# Crumar_D9U_Drawbars.net
KiCad netlist of a schematic drawn in EAGLE
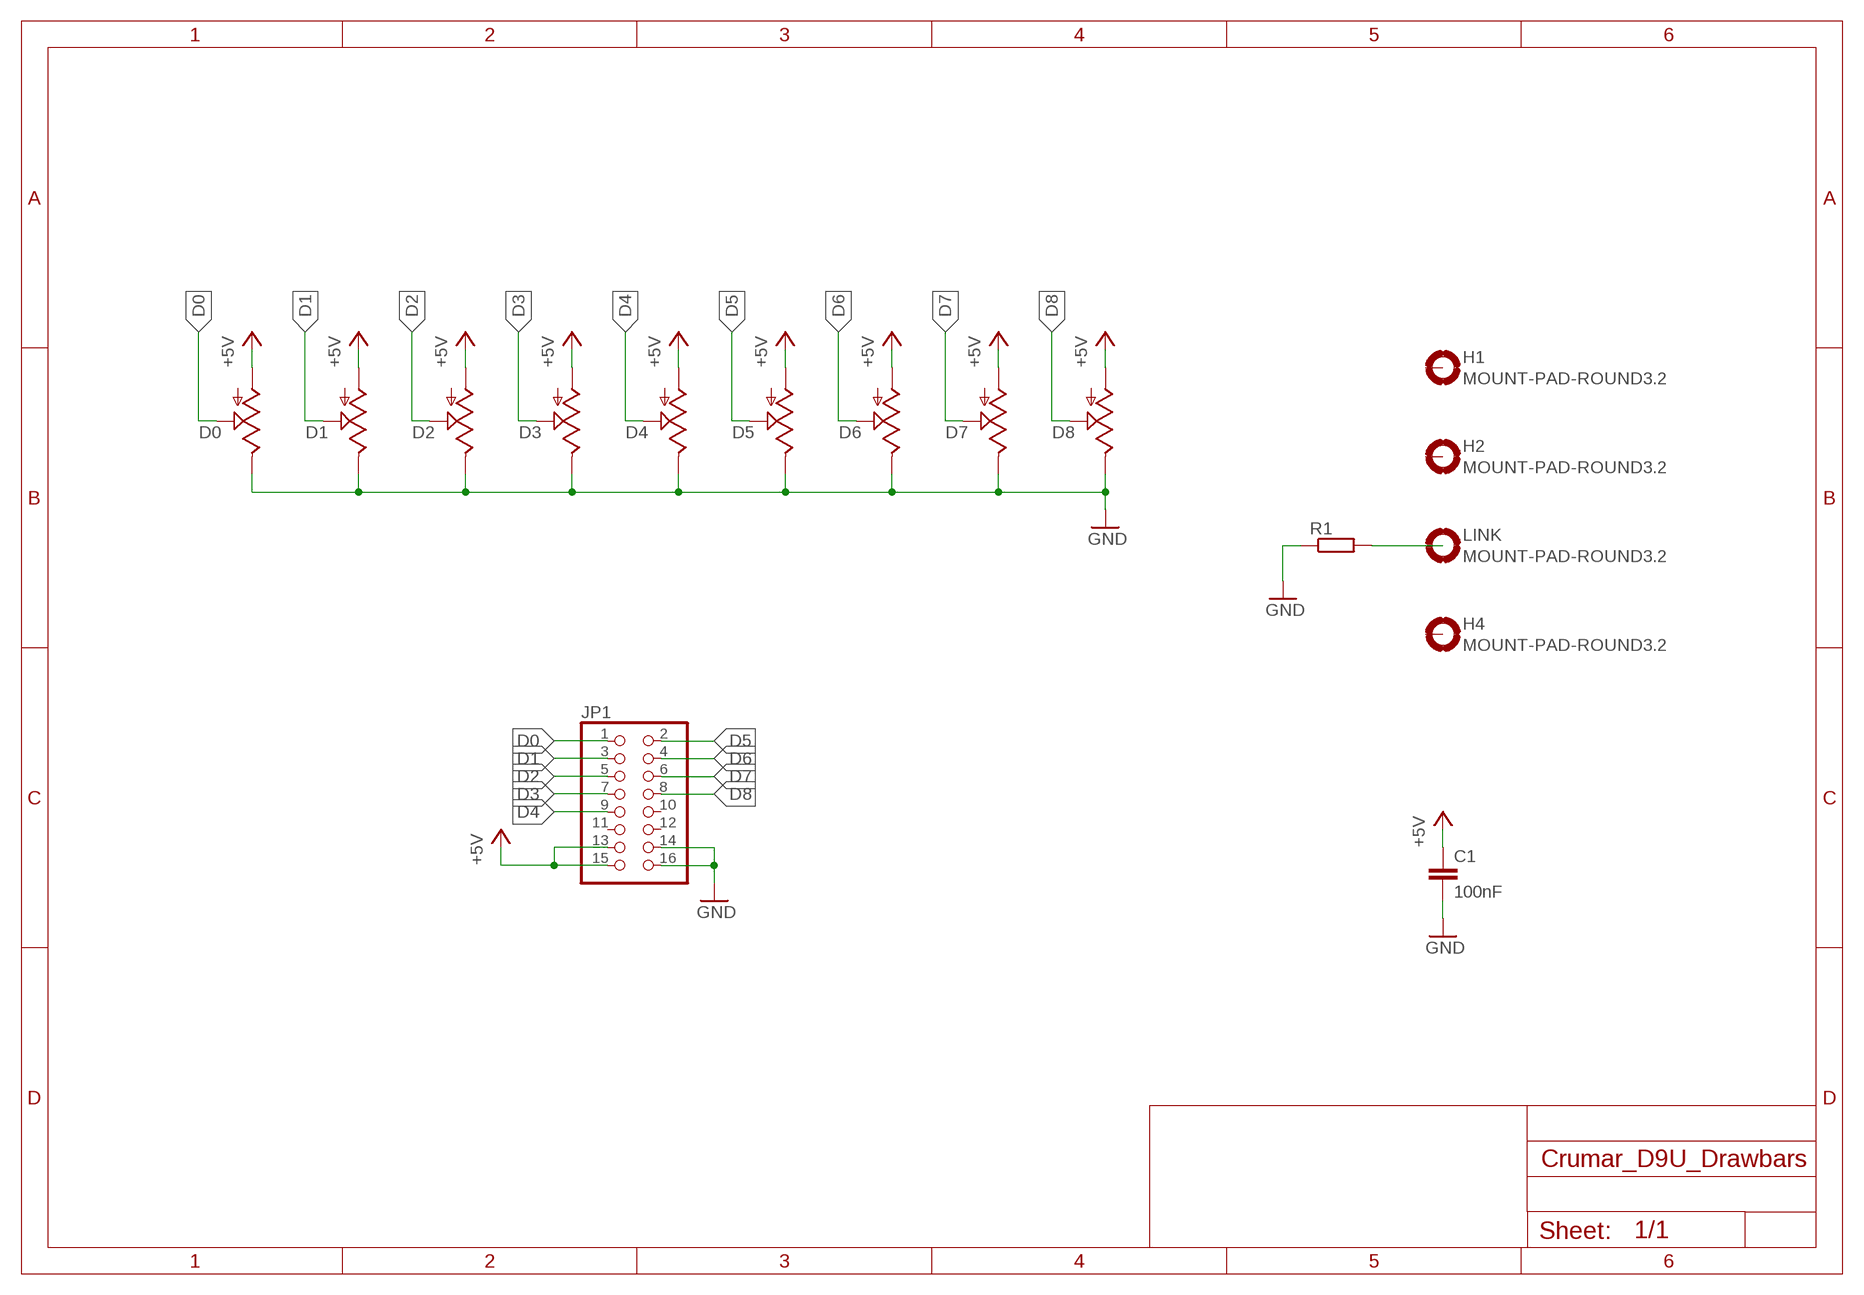
[diagram p0: schematic, sheet 1]

(export (version "E")
  (design (tool "Eeschema 10.0.6"))
  (components
    (comp (ref "C1")
      (value "100nF")
      (footprint "eagle-import:C050-024X044")
      (libsource (lib "eagle-import") (part "C-EU050-024X044"))
    )
    (comp (ref "D0")
      (value "POTENTIOMETER")
      (footprint "eagle-import:ALPHA_DRAWBARS")
      (libsource (lib "eagle-import") (part "POTENTIOMETER"))
    )
    (comp (ref "D1")
      (value "POTENTIOMETER")
      (footprint "eagle-import:ALPHA_DRAWBARS")
      (libsource (lib "eagle-import") (part "POTENTIOMETER"))
    )
    (comp (ref "D2")
      (value "POTENTIOMETER")
      (footprint "eagle-import:ALPHA_DRAWBARS")
      (libsource (lib "eagle-import") (part "POTENTIOMETER"))
    )
    (comp (ref "D3")
      (value "POTENTIOMETER")
      (footprint "eagle-import:ALPHA_DRAWBARS")
      (libsource (lib "eagle-import") (part "POTENTIOMETER"))
    )
    (comp (ref "D4")
      (value "POTENTIOMETER")
      (footprint "eagle-import:ALPHA_DRAWBARS")
      (libsource (lib "eagle-import") (part "POTENTIOMETER"))
    )
    (comp (ref "D5")
      (value "POTENTIOMETER")
      (footprint "eagle-import:ALPHA_DRAWBARS")
      (libsource (lib "eagle-import") (part "POTENTIOMETER"))
    )
    (comp (ref "D6")
      (value "POTENTIOMETER")
      (footprint "eagle-import:ALPHA_DRAWBARS")
      (libsource (lib "eagle-import") (part "POTENTIOMETER"))
    )
    (comp (ref "D7")
      (value "POTENTIOMETER")
      (footprint "eagle-import:ALPHA_DRAWBARS")
      (libsource (lib "eagle-import") (part "POTENTIOMETER"))
    )
    (comp (ref "D8")
      (value "POTENTIOMETER")
      (footprint "eagle-import:ALPHA_DRAWBARS")
      (libsource (lib "eagle-import") (part "POTENTIOMETER"))
    )
    (comp (ref "H1")
      (value "MOUNT-PAD-ROUND3.2")
      (footprint "eagle-import:3,2-PAD")
      (libsource (lib "eagle-import") (part "MOUNT-PAD-ROUND3.2"))
    )
    (comp (ref "H2")
      (value "MOUNT-PAD-ROUND3.2")
      (footprint "eagle-import:3,2-PAD")
      (libsource (lib "eagle-import") (part "MOUNT-PAD-ROUND3.2"))
    )
    (comp (ref "H4")
      (value "MOUNT-PAD-ROUND3.2")
      (footprint "eagle-import:3,2-PAD")
      (libsource (lib "eagle-import") (part "MOUNT-PAD-ROUND3.2"))
    )
    (comp (ref "JP1")
      (value "PINHD-2X8")
      (footprint "eagle-import:2X08")
      (libsource (lib "eagle-import") (part "PINHD-2X8"))
    )
    (comp (ref "LINK")
      (value "MOUNT-PAD-ROUND3.2")
      (footprint "eagle-import:3,2-PAD")
      (libsource (lib "eagle-import") (part "MOUNT-PAD-ROUND3.2"))
    )
    (comp (ref "R1")
      (value "R-EU_0207/12")
      (footprint "eagle-import:0207_12")
      (libsource (lib "eagle-import") (part "R-EU_0207/12"))
    )
  )
  (nets
    (net (code "1") (name "+5V") (class "Default")
      (node (ref "C1") (pin "1") (pinfunction "1_1") (pintype "passive"))
      (node (ref "D0") (pin "P$2") (pinfunction "1_P$2") (pintype "passive"))
      (node (ref "D1") (pin "P$2") (pinfunction "1_P$2") (pintype "passive"))
      (node (ref "D2") (pin "P$2") (pinfunction "1_P$2") (pintype "passive"))
      (node (ref "D3") (pin "P$2") (pinfunction "1_P$2") (pintype "passive"))
      (node (ref "D4") (pin "P$2") (pinfunction "1_P$2") (pintype "passive"))
      (node (ref "D5") (pin "P$2") (pinfunction "1_P$2") (pintype "passive"))
      (node (ref "D6") (pin "P$2") (pinfunction "1_P$2") (pintype "passive"))
      (node (ref "D7") (pin "P$2") (pinfunction "1_P$2") (pintype "passive"))
      (node (ref "D8") (pin "P$2") (pinfunction "1_P$2") (pintype "passive"))
      (node (ref "JP1") (pin "13") (pinfunction "13_13") (pintype "passive"))
      (node (ref "JP1") (pin "15") (pinfunction "15_15") (pintype "passive"))
    )
    (net (code "2") (name "D0") (class "Default")
      (node (ref "D0") (pin "P$3") (pinfunction "2_P$3") (pintype "passive"))
      (node (ref "JP1") (pin "1") (pinfunction "1_1") (pintype "passive"))
    )
    (net (code "3") (name "D1") (class "Default")
      (node (ref "D1") (pin "P$3") (pinfunction "2_P$3") (pintype "passive"))
      (node (ref "JP1") (pin "3") (pinfunction "3_3") (pintype "passive"))
    )
    (net (code "4") (name "D2") (class "Default")
      (node (ref "D2") (pin "P$3") (pinfunction "2_P$3") (pintype "passive"))
      (node (ref "JP1") (pin "5") (pinfunction "5_5") (pintype "passive"))
    )
    (net (code "5") (name "D3") (class "Default")
      (node (ref "D3") (pin "P$3") (pinfunction "2_P$3") (pintype "passive"))
      (node (ref "JP1") (pin "7") (pinfunction "7_7") (pintype "passive"))
    )
    (net (code "6") (name "D4") (class "Default")
      (node (ref "D4") (pin "P$3") (pinfunction "2_P$3") (pintype "passive"))
      (node (ref "JP1") (pin "9") (pinfunction "9_9") (pintype "passive"))
    )
    (net (code "7") (name "D5") (class "Default")
      (node (ref "D5") (pin "P$3") (pinfunction "2_P$3") (pintype "passive"))
      (node (ref "JP1") (pin "2") (pinfunction "2_2") (pintype "passive"))
    )
    (net (code "8") (name "D6") (class "Default")
      (node (ref "D6") (pin "P$3") (pinfunction "2_P$3") (pintype "passive"))
      (node (ref "JP1") (pin "4") (pinfunction "4_4") (pintype "passive"))
    )
    (net (code "9") (name "D7") (class "Default")
      (node (ref "D7") (pin "P$3") (pinfunction "2_P$3") (pintype "passive"))
      (node (ref "JP1") (pin "6") (pinfunction "6_6") (pintype "passive"))
    )
    (net (code "10") (name "D8") (class "Default")
      (node (ref "D8") (pin "P$3") (pinfunction "2_P$3") (pintype "passive"))
      (node (ref "JP1") (pin "8") (pinfunction "8_8") (pintype "passive"))
    )
    (net (code "11") (name "GND") (class "Default")
      (node (ref "C1") (pin "2") (pinfunction "2_2") (pintype "passive"))
      (node (ref "D0") (pin "P$1") (pinfunction "3_P$1") (pintype "passive"))
      (node (ref "D1") (pin "P$1") (pinfunction "3_P$1") (pintype "passive"))
      (node (ref "D2") (pin "P$1") (pinfunction "3_P$1") (pintype "passive"))
      (node (ref "D3") (pin "P$1") (pinfunction "3_P$1") (pintype "passive"))
      (node (ref "D4") (pin "P$1") (pinfunction "3_P$1") (pintype "passive"))
      (node (ref "D5") (pin "P$1") (pinfunction "3_P$1") (pintype "passive"))
      (node (ref "D6") (pin "P$1") (pinfunction "3_P$1") (pintype "passive"))
      (node (ref "D7") (pin "P$1") (pinfunction "3_P$1") (pintype "passive"))
      (node (ref "D8") (pin "P$1") (pinfunction "3_P$1") (pintype "passive"))
      (node (ref "JP1") (pin "14") (pinfunction "14_14") (pintype "passive"))
      (node (ref "JP1") (pin "16") (pinfunction "16_16") (pintype "passive"))
      (node (ref "R1") (pin "1") (pinfunction "1_1") (pintype "passive"))
    )
    (net (code "12") (name "unconnected-(H1-MOUNT-PadB3,2)") (class "Default")
      (node (ref "H1") (pin "B3,2") (pinfunction "MOUNT_B3,2") (pintype "passive"))
    )
    (net (code "13") (name "unconnected-(H2-MOUNT-PadB3,2)") (class "Default")
      (node (ref "H2") (pin "B3,2") (pinfunction "MOUNT_B3,2") (pintype "passive"))
    )
    (net (code "14") (name "unconnected-(H4-MOUNT-PadB3,2)") (class "Default")
      (node (ref "H4") (pin "B3,2") (pinfunction "MOUNT_B3,2") (pintype "passive"))
    )
    (net (code "15") (name "unconnected-(JP1-Pad10)") (class "Default")
      (node (ref "JP1") (pin "10") (pinfunction "10_10") (pintype "passive"))
    )
    (net (code "16") (name "unconnected-(JP1-Pad11)") (class "Default")
      (node (ref "JP1") (pin "11") (pinfunction "11_11") (pintype "passive"))
    )
    (net (code "17") (name "unconnected-(JP1-Pad12)") (class "Default")
      (node (ref "JP1") (pin "12") (pinfunction "12_12") (pintype "passive"))
    )
    (net (code "18") (name "unconnected-(LINK-MOUNT-PadB3,2)") (class "Default")
      (node (ref "LINK") (pin "B3,2") (pinfunction "MOUNT_B3,2") (pintype "passive"))
    )
    (net (code "19") (name "unconnected-(R1-Pad2)") (class "Default")
      (node (ref "R1") (pin "2") (pinfunction "2_2") (pintype "passive"))
    )
  )
)
